# WeWyAn.net
KiCad netlist of a schematic drawn in EAGLE
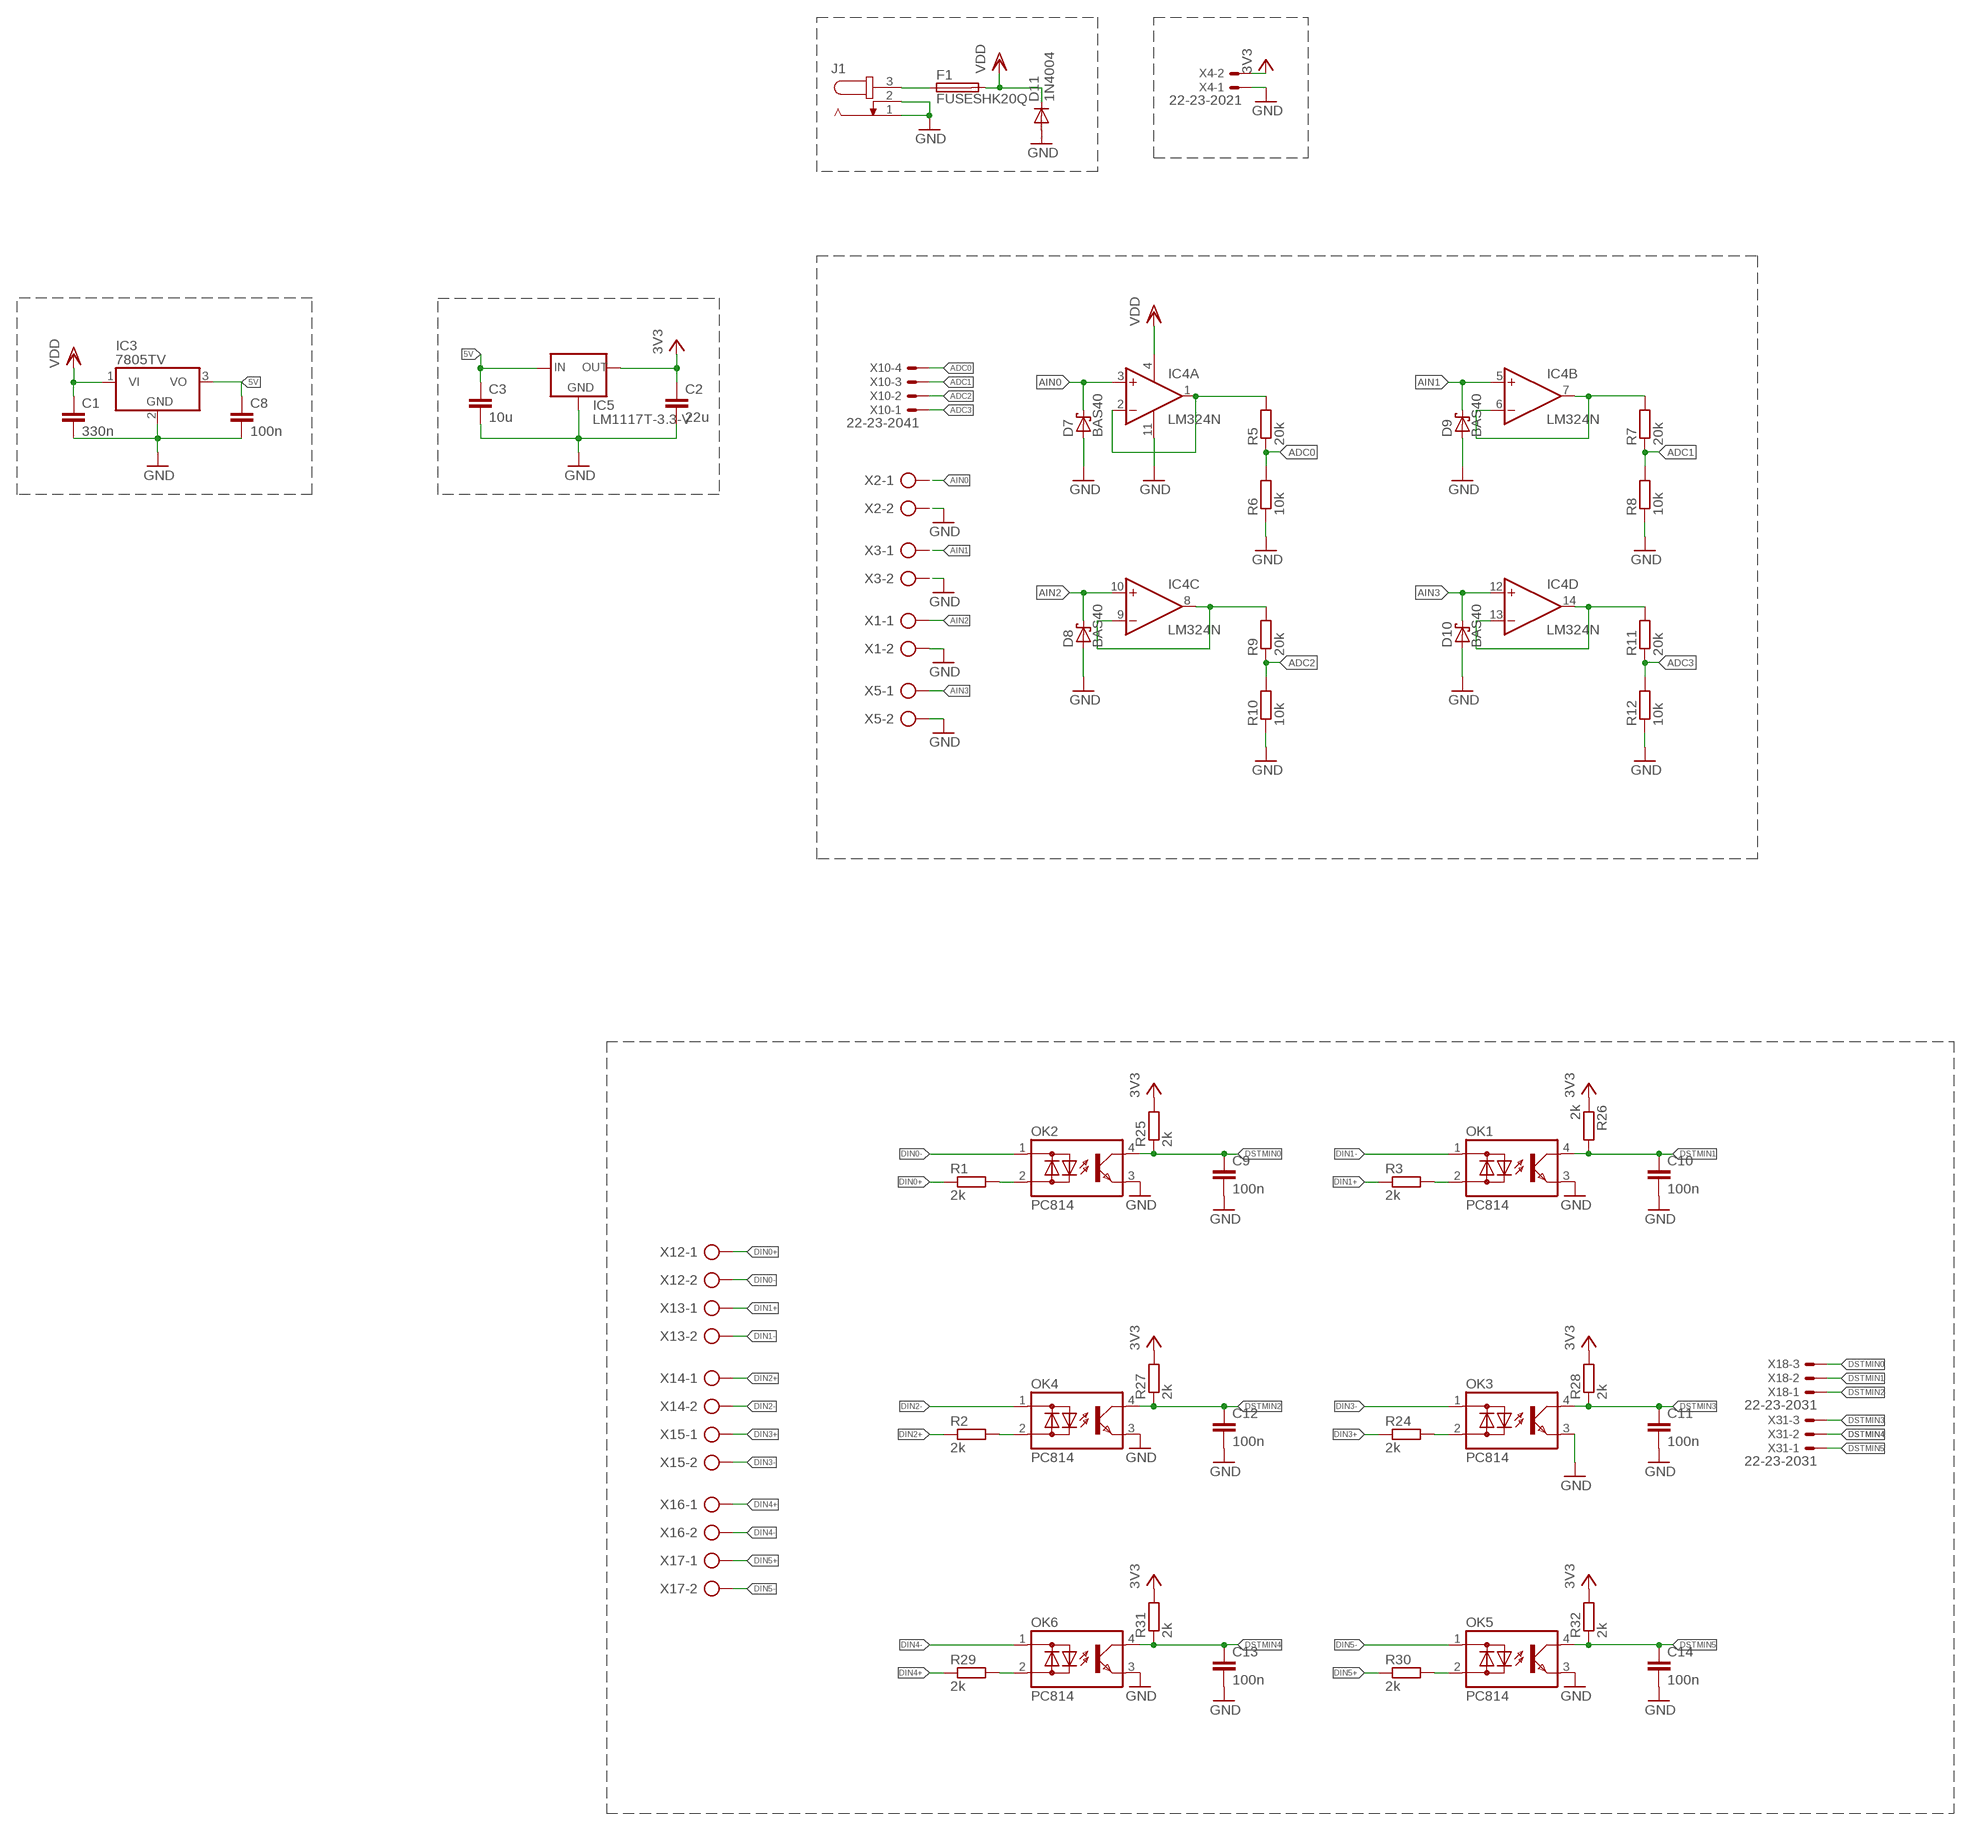
[diagram p0: schematic, sheet 1, part 1 of 2]
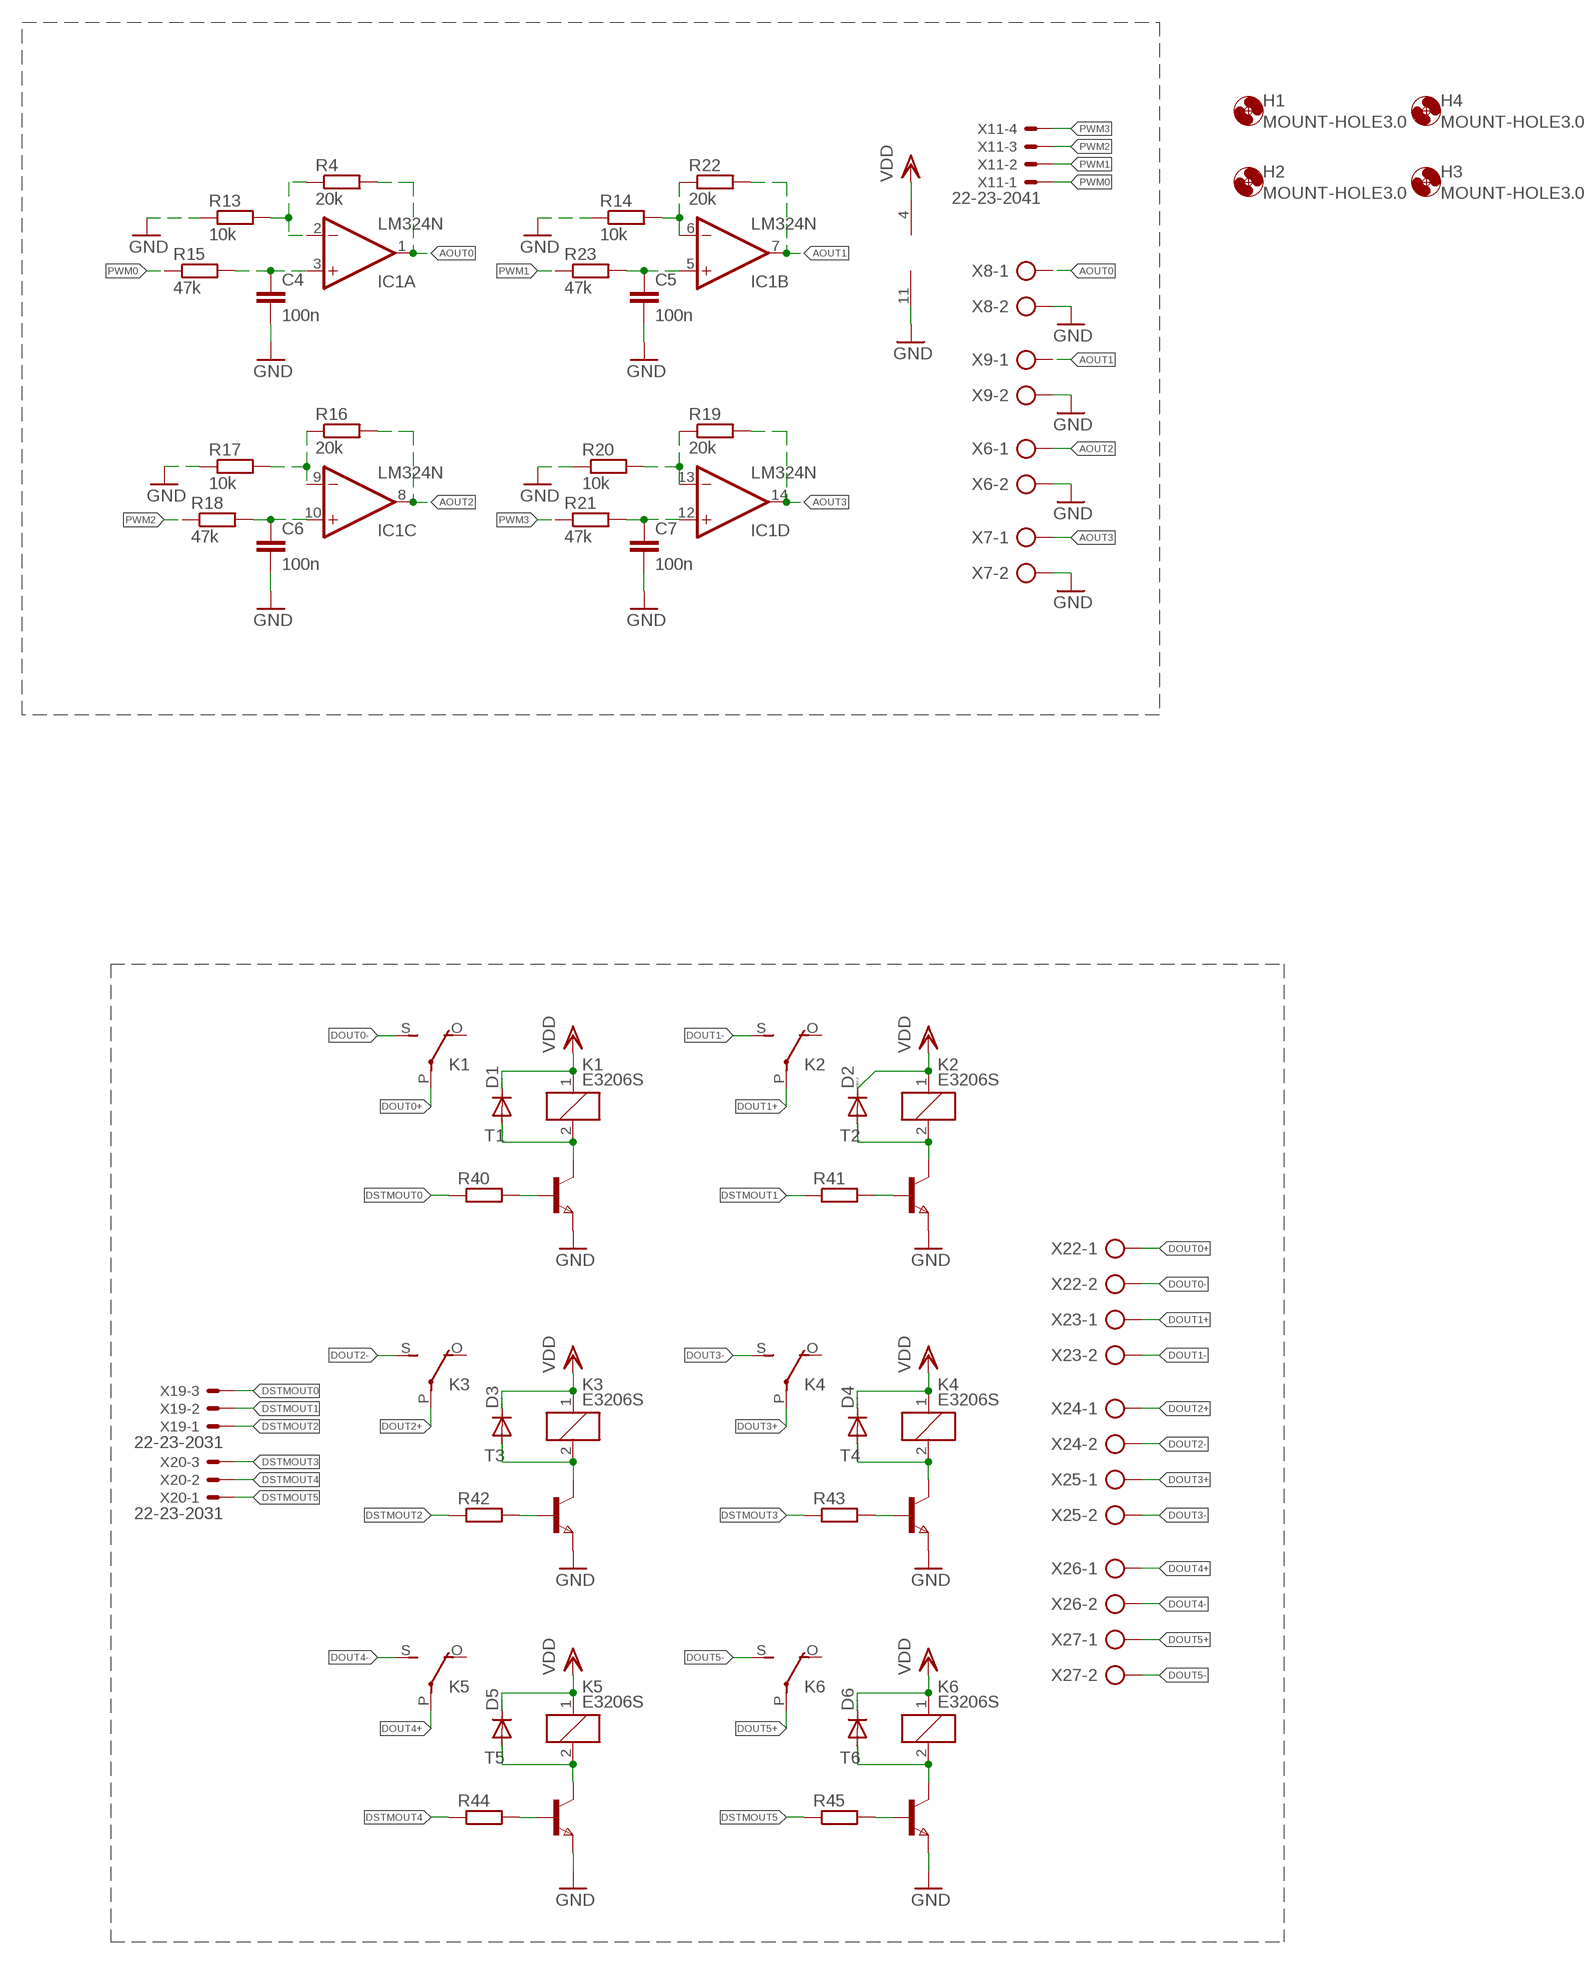
[diagram p1: schematic, sheet 1, part 2 of 2]

(export (version "E")
  (design (tool "Eeschema 10.0.6"))
  (components
    (comp (ref "C1")
      (value "330n")
      (footprint "eagle-import:C0603")
      (libsource (lib "eagle-import") (part "rcl_334_C-EUC0603"))
    )
    (comp (ref "C2")
      (value "22u")
      (footprint "eagle-import:C0603K")
      (libsource (lib "eagle-import") (part "C-EUC0603K"))
    )
    (comp (ref "C3")
      (value "10u")
      (footprint "eagle-import:C0603K")
      (libsource (lib "eagle-import") (part "C-EUC0603K"))
    )
    (comp (ref "C4")
      (value "100n")
      (footprint "eagle-import:C0603K")
      (libsource (lib "eagle-import") (part "C-EUC0603K"))
    )
    (comp (ref "C5")
      (value "100n")
      (footprint "eagle-import:C0603K")
      (libsource (lib "eagle-import") (part "C-EUC0603K"))
    )
    (comp (ref "C6")
      (value "100n")
      (footprint "eagle-import:C0603K")
      (libsource (lib "eagle-import") (part "C-EUC0603K"))
    )
    (comp (ref "C7")
      (value "100n")
      (footprint "eagle-import:C0603K")
      (libsource (lib "eagle-import") (part "C-EUC0603K"))
    )
    (comp (ref "C8")
      (value "100n")
      (footprint "eagle-import:C0603")
      (libsource (lib "eagle-import") (part "rcl_334_C-EUC0603"))
    )
    (comp (ref "C9")
      (value "100n")
      (footprint "eagle-import:C0603")
      (libsource (lib "eagle-import") (part "rcl_334_C-EUC0603"))
    )
    (comp (ref "C10")
      (value "100n")
      (footprint "eagle-import:C0603")
      (libsource (lib "eagle-import") (part "rcl_334_C-EUC0603"))
    )
    (comp (ref "C11")
      (value "100n")
      (footprint "eagle-import:C0603")
      (libsource (lib "eagle-import") (part "rcl_334_C-EUC0603"))
    )
    (comp (ref "C12")
      (value "100n")
      (footprint "eagle-import:C0603")
      (libsource (lib "eagle-import") (part "rcl_334_C-EUC0603"))
    )
    (comp (ref "C13")
      (value "100n")
      (footprint "eagle-import:C0603")
      (libsource (lib "eagle-import") (part "rcl_334_C-EUC0603"))
    )
    (comp (ref "C14")
      (value "100n")
      (footprint "eagle-import:C0603")
      (libsource (lib "eagle-import") (part "rcl_334_C-EUC0603"))
    )
    (comp (ref "D1")
      (value "DIODE-DO214AC")
      (footprint "eagle-import:DO214AC")
      (libsource (lib "eagle-import") (part "DIODE-DO214AC"))
    )
    (comp (ref "D2")
      (value "DIODE-DO214AC")
      (footprint "eagle-import:DO214AC")
      (libsource (lib "eagle-import") (part "DIODE-DO214AC"))
    )
    (comp (ref "D3")
      (value "DIODE-DO214AC")
      (footprint "eagle-import:DO214AC")
      (libsource (lib "eagle-import") (part "DIODE-DO214AC"))
    )
    (comp (ref "D4")
      (value "DIODE-DO214AC")
      (footprint "eagle-import:DO214AC")
      (libsource (lib "eagle-import") (part "DIODE-DO214AC"))
    )
    (comp (ref "D5")
      (value "DIODE-DO214AC")
      (footprint "eagle-import:DO214AC")
      (libsource (lib "eagle-import") (part "DIODE-DO214AC"))
    )
    (comp (ref "D6")
      (value "DIODE-DO214AC")
      (footprint "eagle-import:DO214AC")
      (libsource (lib "eagle-import") (part "DIODE-DO214AC"))
    )
    (comp (ref "D7")
      (value "BAS40")
      (footprint "eagle-import:SOT23")
      (libsource (lib "eagle-import") (part "BAS40"))
    )
    (comp (ref "D8")
      (value "BAS40")
      (footprint "eagle-import:SOT23")
      (libsource (lib "eagle-import") (part "BAS40"))
    )
    (comp (ref "D9")
      (value "BAS40")
      (footprint "eagle-import:SOT23")
      (libsource (lib "eagle-import") (part "BAS40"))
    )
    (comp (ref "D10")
      (value "BAS40")
      (footprint "eagle-import:SOT23")
      (libsource (lib "eagle-import") (part "BAS40"))
    )
    (comp (ref "D11")
      (value "1N4004")
      (footprint "eagle-import:DO41-10")
      (libsource (lib "eagle-import") (part "1N4004"))
    )
    (comp (ref "F1")
      (value "FUSESHK20Q")
      (footprint "eagle-import:SHK20Q")
      (libsource (lib "eagle-import") (part "FUSESHK20Q"))
    )
    (comp (ref "H1")
      (value "MOUNT-HOLE3.0")
      (footprint "eagle-import:3,0")
      (libsource (lib "eagle-import") (part "MOUNT-HOLE3.0"))
    )
    (comp (ref "H2")
      (value "MOUNT-HOLE3.0")
      (footprint "eagle-import:3,0")
      (libsource (lib "eagle-import") (part "MOUNT-HOLE3.0"))
    )
    (comp (ref "H3")
      (value "MOUNT-HOLE3.0")
      (footprint "eagle-import:3,0")
      (libsource (lib "eagle-import") (part "MOUNT-HOLE3.0"))
    )
    (comp (ref "H4")
      (value "MOUNT-HOLE3.0")
      (footprint "eagle-import:3,0")
      (libsource (lib "eagle-import") (part "MOUNT-HOLE3.0"))
    )
    (comp (ref "IC1")
      (value "LM324N")
      (footprint "eagle-import:DIL14")
      (libsource (lib "eagle-import") (part "LM324N"))
    )
    (comp (ref "IC3")
      (value "7805TV")
      (footprint "eagle-import:TO220V")
      (libsource (lib "eagle-import") (part "78TV05"))
    )
    (comp (ref "IC4")
      (value "LM324N")
      (footprint "eagle-import:DIL14")
      (libsource (lib "eagle-import") (part "LM324N"))
    )
    (comp (ref "IC5")
      (value "LM1117T-3.3-V")
      (footprint "eagle-import:TO220V")
      (libsource (lib "eagle-import") (part "LM1117T--V3.3"))
    )
    (comp (ref "J1")
      (value "JACK-PLUG1")
      (footprint "eagle-import:SPC4078")
      (libsource (lib "eagle-import") (part "JACK-PLUG1"))
    )
    (comp (ref "K1")
      (value "E3206S")
      (footprint "eagle-import:E3206S")
      (libsource (lib "eagle-import") (part "E3206S"))
    )
    (comp (ref "K2")
      (value "E3206S")
      (footprint "eagle-import:E3206S")
      (libsource (lib "eagle-import") (part "E3206S"))
    )
    (comp (ref "K3")
      (value "E3206S")
      (footprint "eagle-import:E3206S")
      (libsource (lib "eagle-import") (part "E3206S"))
    )
    (comp (ref "K4")
      (value "E3206S")
      (footprint "eagle-import:E3206S")
      (libsource (lib "eagle-import") (part "E3206S"))
    )
    (comp (ref "K5")
      (value "E3206S")
      (footprint "eagle-import:E3206S")
      (libsource (lib "eagle-import") (part "E3206S"))
    )
    (comp (ref "K6")
      (value "E3206S")
      (footprint "eagle-import:E3206S")
      (libsource (lib "eagle-import") (part "E3206S"))
    )
    (comp (ref "OK1")
      (value "PC814")
      (footprint "eagle-import:DIL04")
      (libsource (lib "eagle-import") (part "PC814"))
    )
    (comp (ref "OK2")
      (value "PC814")
      (footprint "eagle-import:DIL04")
      (libsource (lib "eagle-import") (part "PC814"))
    )
    (comp (ref "OK3")
      (value "PC814")
      (footprint "eagle-import:DIL04")
      (libsource (lib "eagle-import") (part "PC814"))
    )
    (comp (ref "OK4")
      (value "PC814")
      (footprint "eagle-import:DIL04")
      (libsource (lib "eagle-import") (part "PC814"))
    )
    (comp (ref "OK5")
      (value "PC814")
      (footprint "eagle-import:DIL04")
      (libsource (lib "eagle-import") (part "PC814"))
    )
    (comp (ref "OK6")
      (value "PC814")
      (footprint "eagle-import:DIL04")
      (libsource (lib "eagle-import") (part "PC814"))
    )
    (comp (ref "R1")
      (value "2k")
      (footprint "eagle-import:R0603")
      (libsource (lib "eagle-import") (part "R-EU_R0603"))
    )
    (comp (ref "R2")
      (value "2k")
      (footprint "eagle-import:R0603")
      (libsource (lib "eagle-import") (part "R-EU_R0603"))
    )
    (comp (ref "R3")
      (value "2k")
      (footprint "eagle-import:R0603")
      (libsource (lib "eagle-import") (part "R-EU_R0603"))
    )
    (comp (ref "R4")
      (value "20k")
      (footprint "eagle-import:R0603")
      (libsource (lib "eagle-import") (part "R-EU_R0603"))
    )
    (comp (ref "R5")
      (value "20k")
      (footprint "eagle-import:R0603")
      (libsource (lib "eagle-import") (part "R-EU_R0603"))
    )
    (comp (ref "R6")
      (value "10k")
      (footprint "eagle-import:R0603")
      (libsource (lib "eagle-import") (part "R-EU_R0603"))
    )
    (comp (ref "R7")
      (value "20k")
      (footprint "eagle-import:R0603")
      (libsource (lib "eagle-import") (part "R-EU_R0603"))
    )
    (comp (ref "R8")
      (value "10k")
      (footprint "eagle-import:R0603")
      (libsource (lib "eagle-import") (part "R-EU_R0603"))
    )
    (comp (ref "R9")
      (value "20k")
      (footprint "eagle-import:R0603")
      (libsource (lib "eagle-import") (part "R-EU_R0603"))
    )
    (comp (ref "R10")
      (value "10k")
      (footprint "eagle-import:R0603")
      (libsource (lib "eagle-import") (part "R-EU_R0603"))
    )
    (comp (ref "R11")
      (value "20k")
      (footprint "eagle-import:R0603")
      (libsource (lib "eagle-import") (part "R-EU_R0603"))
    )
    (comp (ref "R12")
      (value "10k")
      (footprint "eagle-import:R0603")
      (libsource (lib "eagle-import") (part "R-EU_R0603"))
    )
    (comp (ref "R13")
      (value "10k")
      (footprint "eagle-import:R0603")
      (libsource (lib "eagle-import") (part "R-EU_R0603"))
    )
    (comp (ref "R14")
      (value "10k")
      (footprint "eagle-import:R0603")
      (libsource (lib "eagle-import") (part "R-EU_R0603"))
    )
    (comp (ref "R15")
      (value "47k")
      (footprint "eagle-import:R0603")
      (libsource (lib "eagle-import") (part "R-EU_R0603"))
    )
    (comp (ref "R16")
      (value "20k")
      (footprint "eagle-import:R0603")
      (libsource (lib "eagle-import") (part "R-EU_R0603"))
    )
    (comp (ref "R17")
      (value "10k")
      (footprint "eagle-import:R0603")
      (libsource (lib "eagle-import") (part "R-EU_R0603"))
    )
    (comp (ref "R18")
      (value "47k")
      (footprint "eagle-import:R0603")
      (libsource (lib "eagle-import") (part "R-EU_R0603"))
    )
    (comp (ref "R19")
      (value "20k")
      (footprint "eagle-import:R0603")
      (libsource (lib "eagle-import") (part "R-EU_R0603"))
    )
    (comp (ref "R20")
      (value "10k")
      (footprint "eagle-import:R0603")
      (libsource (lib "eagle-import") (part "R-EU_R0603"))
    )
    (comp (ref "R21")
      (value "47k")
      (footprint "eagle-import:R0603")
      (libsource (lib "eagle-import") (part "R-EU_R0603"))
    )
    (comp (ref "R22")
      (value "20k")
      (footprint "eagle-import:R0603")
      (libsource (lib "eagle-import") (part "R-EU_R0603"))
    )
    (comp (ref "R23")
      (value "47k")
      (footprint "eagle-import:R0603")
      (libsource (lib "eagle-import") (part "R-EU_R0603"))
    )
    (comp (ref "R24")
      (value "2k")
      (footprint "eagle-import:R0603")
      (libsource (lib "eagle-import") (part "R-EU_R0603"))
    )
    (comp (ref "R25")
      (value "2k")
      (footprint "eagle-import:R0603")
      (libsource (lib "eagle-import") (part "R-EU_R0603"))
    )
    (comp (ref "R26")
      (value "2k")
      (footprint "eagle-import:R0603")
      (libsource (lib "eagle-import") (part "R-EU_R0603"))
    )
    (comp (ref "R27")
      (value "2k")
      (footprint "eagle-import:R0603")
      (libsource (lib "eagle-import") (part "R-EU_R0603"))
    )
    (comp (ref "R28")
      (value "2k")
      (footprint "eagle-import:R0603")
      (libsource (lib "eagle-import") (part "R-EU_R0603"))
    )
    (comp (ref "R29")
      (value "2k")
      (footprint "eagle-import:R0603")
      (libsource (lib "eagle-import") (part "R-EU_R0603"))
    )
    (comp (ref "R30")
      (value "2k")
      (footprint "eagle-import:R0603")
      (libsource (lib "eagle-import") (part "R-EU_R0603"))
    )
    (comp (ref "R31")
      (value "2k")
      (footprint "eagle-import:R0603")
      (libsource (lib "eagle-import") (part "R-EU_R0603"))
    )
    (comp (ref "R32")
      (value "2k")
      (footprint "eagle-import:R0603")
      (libsource (lib "eagle-import") (part "R-EU_R0603"))
    )
    (comp (ref "R40")
      (value "R-EU_R0603")
      (footprint "eagle-import:R0603")
      (libsource (lib "eagle-import") (part "rcl_334_R-EU_R0603"))
    )
    (comp (ref "R41")
      (value "R-EU_R0603")
      (footprint "eagle-import:R0603")
      (libsource (lib "eagle-import") (part "rcl_334_R-EU_R0603"))
    )
    (comp (ref "R42")
      (value "R-EU_R0603")
      (footprint "eagle-import:R0603")
      (libsource (lib "eagle-import") (part "rcl_334_R-EU_R0603"))
    )
    (comp (ref "R43")
      (value "R-EU_R0603")
      (footprint "eagle-import:R0603")
      (libsource (lib "eagle-import") (part "rcl_334_R-EU_R0603"))
    )
    (comp (ref "R44")
      (value "R-EU_R0603")
      (footprint "eagle-import:R0603")
      (libsource (lib "eagle-import") (part "rcl_334_R-EU_R0603"))
    )
    (comp (ref "R45")
      (value "R-EU_R0603")
      (footprint "eagle-import:R0603")
      (libsource (lib "eagle-import") (part "rcl_334_R-EU_R0603"))
    )
    (comp (ref "T1")
      (value "NPNSOT223")
      (footprint "eagle-import:SOT223")
      (fields (field (name "MPN") "DJT4031N-13"))
      (libsource (lib "eagle-import") (part "NPNSOT223"))
    )
    (comp (ref "T2")
      (value "NPNSOT223")
      (footprint "eagle-import:SOT223")
      (fields (field (name "MPN") "DJT4031N-13"))
      (libsource (lib "eagle-import") (part "NPNSOT223"))
    )
    (comp (ref "T3")
      (value "NPNSOT223")
      (footprint "eagle-import:SOT223")
      (fields (field (name "MPN") "DJT4031N-13"))
      (libsource (lib "eagle-import") (part "NPNSOT223"))
    )
    (comp (ref "T4")
      (value "NPNSOT223")
      (footprint "eagle-import:SOT223")
      (fields (field (name "MPN") "DJT4031N-13"))
      (libsource (lib "eagle-import") (part "NPNSOT223"))
    )
    (comp (ref "T5")
      (value "NPNSOT223")
      (footprint "eagle-import:SOT223")
      (fields (field (name "MPN") "DJT4031N-13"))
      (libsource (lib "eagle-import") (part "NPNSOT223"))
    )
    (comp (ref "T6")
      (value "NPNSOT223")
      (footprint "eagle-import:SOT223")
      (fields (field (name "MPN") "DJT4031N-13"))
      (libsource (lib "eagle-import") (part "NPNSOT223"))
    )
    (comp (ref "X1")
      (value "AK500/2-H")
      (footprint "eagle-import:AK500_2-H")
      (libsource (lib "eagle-import") (part "AK500/2-H"))
    )
    (comp (ref "X2")
      (value "AK500/2-H")
      (footprint "eagle-import:AK500_2-H")
      (libsource (lib "eagle-import") (part "AK500/2-H"))
    )
    (comp (ref "X3")
      (value "AK500/2-H")
      (footprint "eagle-import:AK500_2-H")
      (libsource (lib "eagle-import") (part "AK500/2-H"))
    )
    (comp (ref "X4")
      (value "22-23-2021")
      (footprint "eagle-import:22-23-2021")
      (fields (field (name "MF") "MOLEX"))
      (libsource (lib "eagle-import") (part "22-23-2021"))
    )
    (comp (ref "X5")
      (value "AK500/2-H")
      (footprint "eagle-import:AK500_2-H")
      (libsource (lib "eagle-import") (part "AK500/2-H"))
    )
    (comp (ref "X6")
      (value "AK500/2-H")
      (footprint "eagle-import:AK500_2-H")
      (libsource (lib "eagle-import") (part "AK500/2-H"))
    )
    (comp (ref "X7")
      (value "AK500/2-H")
      (footprint "eagle-import:AK500_2-H")
      (libsource (lib "eagle-import") (part "AK500/2-H"))
    )
    (comp (ref "X8")
      (value "AK500/2-H")
      (footprint "eagle-import:AK500_2-H")
      (libsource (lib "eagle-import") (part "AK500/2-H"))
    )
    (comp (ref "X9")
      (value "AK500/2-H")
      (footprint "eagle-import:AK500_2-H")
      (libsource (lib "eagle-import") (part "AK500/2-H"))
    )
    (comp (ref "X10")
      (value "22-23-2041")
      (footprint "eagle-import:22-23-2041")
      (fields (field (name "MF") "MOLEX"))
      (libsource (lib "eagle-import") (part "22-23-2041"))
    )
    (comp (ref "X11")
      (value "22-23-2041")
      (footprint "eagle-import:22-23-2041")
      (fields (field (name "MF") "MOLEX"))
      (libsource (lib "eagle-import") (part "22-23-2041"))
    )
    (comp (ref "X12")
      (value "AK500/2-H")
      (footprint "eagle-import:AK500_2-H")
      (libsource (lib "eagle-import") (part "AK500/2-H"))
    )
    (comp (ref "X13")
      (value "AK500/2-H")
      (footprint "eagle-import:AK500_2-H")
      (libsource (lib "eagle-import") (part "AK500/2-H"))
    )
    (comp (ref "X14")
      (value "AK500/2-H")
      (footprint "eagle-import:AK500_2-H")
      (libsource (lib "eagle-import") (part "AK500/2-H"))
    )
    (comp (ref "X15")
      (value "AK500/2-H")
      (footprint "eagle-import:AK500_2-H")
      (libsource (lib "eagle-import") (part "AK500/2-H"))
    )
    (comp (ref "X16")
      (value "AK500/2-H")
      (footprint "eagle-import:AK500_2-H")
      (libsource (lib "eagle-import") (part "AK500/2-H"))
    )
    (comp (ref "X17")
      (value "AK500/2-H")
      (footprint "eagle-import:AK500_2-H")
      (libsource (lib "eagle-import") (part "AK500/2-H"))
    )
    (comp (ref "X18")
      (value "22-23-2031")
      (footprint "eagle-import:22-23-2031")
      (fields (field (name "MF") "MOLEX"))
      (libsource (lib "eagle-import") (part "22-23-2031"))
    )
    (comp (ref "X19")
      (value "22-23-2031")
      (footprint "eagle-import:22-23-2031")
      (fields (field (name "MF") "MOLEX"))
      (libsource (lib "eagle-import") (part "22-23-2031"))
    )
    (comp (ref "X20")
      (value "22-23-2031")
      (footprint "eagle-import:22-23-2031")
      (fields (field (name "MF") "MOLEX"))
      (libsource (lib "eagle-import") (part "22-23-2031"))
    )
    (comp (ref "X22")
      (value "AK500/2-H")
      (footprint "eagle-import:AK500_2-H")
      (libsource (lib "eagle-import") (part "AK500/2-H"))
    )
    (comp (ref "X23")
      (value "AK500/2-H")
      (footprint "eagle-import:AK500_2-H")
      (libsource (lib "eagle-import") (part "AK500/2-H"))
    )
    (comp (ref "X24")
      (value "AK500/2-H")
      (footprint "eagle-import:AK500_2-H")
      (libsource (lib "eagle-import") (part "AK500/2-H"))
    )
    (comp (ref "X25")
      (value "AK500/2-H")
      (footprint "eagle-import:AK500_2-H")
      (libsource (lib "eagle-import") (part "AK500/2-H"))
    )
    (comp (ref "X26")
      (value "AK500/2-H")
      (footprint "eagle-import:AK500_2-H")
      (libsource (lib "eagle-import") (part "AK500/2-H"))
    )
    (comp (ref "X27")
      (value "AK500/2-H")
      (footprint "eagle-import:AK500_2-H")
      (libsource (lib "eagle-import") (part "AK500/2-H"))
    )
    (comp (ref "X31")
      (value "22-23-2031")
      (footprint "eagle-import:22-23-2031")
      (fields (field (name "MF") "MOLEX"))
      (libsource (lib "eagle-import") (part "22-23-2031"))
    )
  )
  (nets
    (net (code "1") (name "3V3") (class "Default")
      (node (ref "C2") (pin "1") (pinfunction "1_1") (pintype "passive"))
      (node (ref "IC5") (pin "2") (pinfunction "OUT_2") (pintype "passive"))
      (node (ref "R25") (pin "2") (pinfunction "2_2") (pintype "passive"))
      (node (ref "R26") (pin "1") (pinfunction "1_1") (pintype "passive"))
      (node (ref "R27") (pin "2") (pinfunction "2_2") (pintype "passive"))
      (node (ref "R28") (pin "2") (pinfunction "2_2") (pintype "passive"))
      (node (ref "R31") (pin "2") (pinfunction "2_2") (pintype "passive"))
      (node (ref "R32") (pin "2") (pinfunction "2_2") (pintype "passive"))
      (node (ref "X4") (pin "2") (pinfunction "S_2") (pintype "passive"))
    )
    (net (code "2") (name "5V") (class "Default")
      (node (ref "C3") (pin "1") (pinfunction "1_1") (pintype "passive"))
      (node (ref "C8") (pin "1") (pinfunction "1_1") (pintype "passive"))
      (node (ref "IC3") (pin "3") (pinfunction "VO_3") (pintype "passive"))
      (node (ref "IC5") (pin "3") (pinfunction "IN_3") (pintype "input"))
    )
    (net (code "3") (name "ADC0") (class "Default")
      (node (ref "R5") (pin "1") (pinfunction "1_1") (pintype "passive"))
      (node (ref "R6") (pin "2") (pinfunction "2_2") (pintype "passive"))
      (node (ref "X10") (pin "4") (pinfunction "S_4") (pintype "passive"))
    )
    (net (code "4") (name "ADC1") (class "Default")
      (node (ref "R7") (pin "1") (pinfunction "1_1") (pintype "passive"))
      (node (ref "R8") (pin "2") (pinfunction "2_2") (pintype "passive"))
      (node (ref "X10") (pin "3") (pinfunction "S_3") (pintype "passive"))
    )
    (net (code "5") (name "ADC2") (class "Default")
      (node (ref "R10") (pin "2") (pinfunction "2_2") (pintype "passive"))
      (node (ref "R9") (pin "1") (pinfunction "1_1") (pintype "passive"))
      (node (ref "X10") (pin "2") (pinfunction "S_2") (pintype "passive"))
    )
    (net (code "6") (name "ADC3") (class "Default")
      (node (ref "R11") (pin "1") (pinfunction "1_1") (pintype "passive"))
      (node (ref "R12") (pin "2") (pinfunction "2_2") (pintype "passive"))
      (node (ref "X10") (pin "1") (pinfunction "S_1") (pintype "passive"))
    )
    (net (code "7") (name "AIN0") (class "Default")
      (node (ref "D7") (pin "3") (pinfunction "C_3") (pintype "passive"))
      (node (ref "IC4") (pin "3") (pinfunction "+IN_3") (pintype "input"))
      (node (ref "X2") (pin "1") (pinfunction "KL_1") (pintype "passive"))
    )
    (net (code "8") (name "AIN1") (class "Default")
      (node (ref "D9") (pin "3") (pinfunction "C_3") (pintype "passive"))
      (node (ref "IC4") (pin "5") (pinfunction "+IN_5") (pintype "input"))
      (node (ref "X3") (pin "1") (pinfunction "KL_1") (pintype "passive"))
    )
    (net (code "9") (name "AIN2") (class "Default")
      (node (ref "D8") (pin "3") (pinfunction "C_3") (pintype "passive"))
      (node (ref "IC4") (pin "10") (pinfunction "+IN_10") (pintype "input"))
      (node (ref "X1") (pin "1") (pinfunction "KL_1") (pintype "passive"))
    )
    (net (code "10") (name "AIN3") (class "Default")
      (node (ref "D10") (pin "3") (pinfunction "C_3") (pintype "passive"))
      (node (ref "IC4") (pin "12") (pinfunction "+IN_12") (pintype "input"))
      (node (ref "X5") (pin "1") (pinfunction "KL_1") (pintype "passive"))
    )
    (net (code "11") (name "AOUT0") (class "Default")
      (node (ref "IC1") (pin "1") (pinfunction "OUT_1") (pintype "output"))
      (node (ref "R4") (pin "2") (pinfunction "2_2") (pintype "passive"))
      (node (ref "X8") (pin "1") (pinfunction "KL_1") (pintype "passive"))
    )
    (net (code "12") (name "AOUT1") (class "Default")
      (node (ref "IC1") (pin "7") (pinfunction "OUT_7") (pintype "output"))
      (node (ref "R22") (pin "2") (pinfunction "2_2") (pintype "passive"))
      (node (ref "X9") (pin "1") (pinfunction "KL_1") (pintype "passive"))
    )
    (net (code "13") (name "AOUT2") (class "Default")
      (node (ref "IC1") (pin "8") (pinfunction "OUT_8") (pintype "output"))
      (node (ref "R16") (pin "2") (pinfunction "2_2") (pintype "passive"))
      (node (ref "X6") (pin "1") (pinfunction "KL_1") (pintype "passive"))
    )
    (net (code "14") (name "AOUT3") (class "Default")
      (node (ref "IC1") (pin "14") (pinfunction "OUT_14") (pintype "output"))
      (node (ref "R19") (pin "2") (pinfunction "2_2") (pintype "passive"))
      (node (ref "X7") (pin "1") (pinfunction "KL_1") (pintype "passive"))
    )
    (net (code "15") (name "DIN0+") (class "Default")
      (node (ref "R1") (pin "1") (pinfunction "1_1") (pintype "passive"))
      (node (ref "X12") (pin "1") (pinfunction "KL_1") (pintype "passive"))
    )
    (net (code "16") (name "DIN0-") (class "Default")
      (node (ref "OK2") (pin "1") (pinfunction "AC1_1") (pintype "passive"))
      (node (ref "X12") (pin "2") (pinfunction "KL_2") (pintype "passive"))
    )
    (net (code "17") (name "DIN1+") (class "Default")
      (node (ref "R3") (pin "1") (pinfunction "1_1") (pintype "passive"))
      (node (ref "X13") (pin "1") (pinfunction "KL_1") (pintype "passive"))
    )
    (net (code "18") (name "DIN1-") (class "Default")
      (node (ref "OK1") (pin "1") (pinfunction "AC1_1") (pintype "passive"))
      (node (ref "X13") (pin "2") (pinfunction "KL_2") (pintype "passive"))
    )
    (net (code "19") (name "DIN2+") (class "Default")
      (node (ref "R2") (pin "1") (pinfunction "1_1") (pintype "passive"))
      (node (ref "X14") (pin "1") (pinfunction "KL_1") (pintype "passive"))
    )
    (net (code "20") (name "DIN2-") (class "Default")
      (node (ref "OK4") (pin "1") (pinfunction "AC1_1") (pintype "passive"))
      (node (ref "X14") (pin "2") (pinfunction "KL_2") (pintype "passive"))
    )
    (net (code "21") (name "DIN3+") (class "Default")
      (node (ref "R24") (pin "1") (pinfunction "1_1") (pintype "passive"))
      (node (ref "X15") (pin "1") (pinfunction "KL_1") (pintype "passive"))
    )
    (net (code "22") (name "DIN3-") (class "Default")
      (node (ref "OK3") (pin "1") (pinfunction "AC1_1") (pintype "passive"))
      (node (ref "X15") (pin "2") (pinfunction "KL_2") (pintype "passive"))
    )
    (net (code "23") (name "DIN4+") (class "Default")
      (node (ref "R29") (pin "1") (pinfunction "1_1") (pintype "passive"))
      (node (ref "X16") (pin "1") (pinfunction "KL_1") (pintype "passive"))
    )
    (net (code "24") (name "DIN4-") (class "Default")
      (node (ref "OK6") (pin "1") (pinfunction "AC1_1") (pintype "passive"))
      (node (ref "X16") (pin "2") (pinfunction "KL_2") (pintype "passive"))
    )
    (net (code "25") (name "DIN5+") (class "Default")
      (node (ref "R30") (pin "1") (pinfunction "1_1") (pintype "passive"))
      (node (ref "X17") (pin "1") (pinfunction "KL_1") (pintype "passive"))
    )
    (net (code "26") (name "DIN5-") (class "Default")
      (node (ref "OK5") (pin "1") (pinfunction "AC1_1") (pintype "passive"))
      (node (ref "X17") (pin "2") (pinfunction "KL_2") (pintype "passive"))
    )
    (net (code "27") (name "DOUT0+") (class "Default")
      (node (ref "K1") (pin "P") (pinfunction "P_P") (pintype "passive"))
      (node (ref "X22") (pin "1") (pinfunction "KL_1") (pintype "passive"))
    )
    (net (code "28") (name "DOUT0-") (class "Default")
      (node (ref "K1") (pin "S") (pinfunction "S_S") (pintype "passive"))
      (node (ref "X22") (pin "2") (pinfunction "KL_2") (pintype "passive"))
    )
    (net (code "29") (name "DOUT1+") (class "Default")
      (node (ref "K2") (pin "P") (pinfunction "P_P") (pintype "passive"))
      (node (ref "X23") (pin "1") (pinfunction "KL_1") (pintype "passive"))
    )
    (net (code "30") (name "DOUT1-") (class "Default")
      (node (ref "K2") (pin "S") (pinfunction "S_S") (pintype "passive"))
      (node (ref "X23") (pin "2") (pinfunction "KL_2") (pintype "passive"))
    )
    (net (code "31") (name "DOUT2+") (class "Default")
      (node (ref "K3") (pin "P") (pinfunction "P_P") (pintype "passive"))
      (node (ref "X24") (pin "1") (pinfunction "KL_1") (pintype "passive"))
    )
    (net (code "32") (name "DOUT2-") (class "Default")
      (node (ref "K3") (pin "S") (pinfunction "S_S") (pintype "passive"))
      (node (ref "X24") (pin "2") (pinfunction "KL_2") (pintype "passive"))
    )
    (net (code "33") (name "DOUT3+") (class "Default")
      (node (ref "K4") (pin "P") (pinfunction "P_P") (pintype "passive"))
      (node (ref "X25") (pin "1") (pinfunction "KL_1") (pintype "passive"))
    )
    (net (code "34") (name "DOUT3-") (class "Default")
      (node (ref "K4") (pin "S") (pinfunction "S_S") (pintype "passive"))
      (node (ref "X25") (pin "2") (pinfunction "KL_2") (pintype "passive"))
    )
    (net (code "35") (name "DOUT4+") (class "Default")
      (node (ref "K5") (pin "P") (pinfunction "P_P") (pintype "passive"))
      (node (ref "X26") (pin "1") (pinfunction "KL_1") (pintype "passive"))
    )
    (net (code "36") (name "DOUT4-") (class "Default")
      (node (ref "K5") (pin "S") (pinfunction "S_S") (pintype "passive"))
      (node (ref "X26") (pin "2") (pinfunction "KL_2") (pintype "passive"))
    )
    (net (code "37") (name "DOUT5+") (class "Default")
      (node (ref "K6") (pin "P") (pinfunction "P_P") (pintype "passive"))
      (node (ref "X27") (pin "1") (pinfunction "KL_1") (pintype "passive"))
    )
    (net (code "38") (name "DOUT5-") (class "Default")
      (node (ref "K6") (pin "S") (pinfunction "S_S") (pintype "passive"))
      (node (ref "X27") (pin "2") (pinfunction "KL_2") (pintype "passive"))
    )
    (net (code "39") (name "DSTMIN0") (class "Default")
      (node (ref "C9") (pin "1") (pinfunction "1_1") (pintype "passive"))
      (node (ref "OK2") (pin "4") (pinfunction "C_4") (pintype "passive"))
      (node (ref "R25") (pin "1") (pinfunction "1_1") (pintype "passive"))
      (node (ref "X18") (pin "3") (pinfunction "S_3") (pintype "passive"))
    )
    (net (code "40") (name "DSTMIN1") (class "Default")
      (node (ref "C10") (pin "1") (pinfunction "1_1") (pintype "passive"))
      (node (ref "OK1") (pin "4") (pinfunction "C_4") (pintype "passive"))
      (node (ref "R26") (pin "2") (pinfunction "2_2") (pintype "passive"))
      (node (ref "X18") (pin "2") (pinfunction "S_2") (pintype "passive"))
    )
    (net (code "41") (name "DSTMIN2") (class "Default")
      (node (ref "C12") (pin "1") (pinfunction "1_1") (pintype "passive"))
      (node (ref "OK4") (pin "4") (pinfunction "C_4") (pintype "passive"))
      (node (ref "R27") (pin "1") (pinfunction "1_1") (pintype "passive"))
      (node (ref "X18") (pin "1") (pinfunction "S_1") (pintype "passive"))
    )
    (net (code "42") (name "DSTMIN3") (class "Default")
      (node (ref "C11") (pin "1") (pinfunction "1_1") (pintype "passive"))
      (node (ref "OK3") (pin "4") (pinfunction "C_4") (pintype "passive"))
      (node (ref "R28") (pin "1") (pinfunction "1_1") (pintype "passive"))
      (node (ref "X31") (pin "3") (pinfunction "S_3") (pintype "passive"))
    )
    (net (code "43") (name "DSTMIN4") (class "Default")
      (node (ref "C13") (pin "1") (pinfunction "1_1") (pintype "passive"))
      (node (ref "OK6") (pin "4") (pinfunction "C_4") (pintype "passive"))
      (node (ref "R31") (pin "1") (pinfunction "1_1") (pintype "passive"))
      (node (ref "X31") (pin "2") (pinfunction "S_2") (pintype "passive"))
    )
    (net (code "44") (name "DSTMIN5") (class "Default")
      (node (ref "C14") (pin "1") (pinfunction "1_1") (pintype "passive"))
      (node (ref "OK5") (pin "4") (pinfunction "C_4") (pintype "passive"))
      (node (ref "R32") (pin "1") (pinfunction "1_1") (pintype "passive"))
      (node (ref "X31") (pin "1") (pinfunction "S_1") (pintype "passive"))
    )
    (net (code "45") (name "DSTMOUT0") (class "Default")
      (node (ref "R40") (pin "1") (pinfunction "1_1") (pintype "passive"))
      (node (ref "X19") (pin "3") (pinfunction "S_3") (pintype "passive"))
    )
    (net (code "46") (name "DSTMOUT1") (class "Default")
      (node (ref "R41") (pin "1") (pinfunction "1_1") (pintype "passive"))
      (node (ref "X19") (pin "2") (pinfunction "S_2") (pintype "passive"))
    )
    (net (code "47") (name "DSTMOUT2") (class "Default")
      (node (ref "R42") (pin "1") (pinfunction "1_1") (pintype "passive"))
      (node (ref "X19") (pin "1") (pinfunction "S_1") (pintype "passive"))
    )
    (net (code "48") (name "DSTMOUT3") (class "Default")
      (node (ref "R43") (pin "1") (pinfunction "1_1") (pintype "passive"))
      (node (ref "X20") (pin "3") (pinfunction "S_3") (pintype "passive"))
    )
    (net (code "49") (name "DSTMOUT4") (class "Default")
      (node (ref "R44") (pin "1") (pinfunction "1_1") (pintype "passive"))
      (node (ref "X20") (pin "2") (pinfunction "S_2") (pintype "passive"))
    )
    (net (code "50") (name "DSTMOUT5") (class "Default")
      (node (ref "R45") (pin "1") (pinfunction "1_1") (pintype "passive"))
      (node (ref "X20") (pin "1") (pinfunction "S_1") (pintype "passive"))
    )
    (net (code "51") (name "GND") (class "Default")
      (node (ref "C1") (pin "2") (pinfunction "2_2") (pintype "passive"))
      (node (ref "C10") (pin "2") (pinfunction "2_2") (pintype "passive"))
      (node (ref "C11") (pin "2") (pinfunction "2_2") (pintype "passive"))
      (node (ref "C12") (pin "2") (pinfunction "2_2") (pintype "passive"))
      (node (ref "C13") (pin "2") (pinfunction "2_2") (pintype "passive"))
      (node (ref "C14") (pin "2") (pinfunction "2_2") (pintype "passive"))
      (node (ref "C2") (pin "2") (pinfunction "2_2") (pintype "passive"))
      (node (ref "C3") (pin "2") (pinfunction "2_2") (pintype "passive"))
      (node (ref "C4") (pin "2") (pinfunction "2_2") (pintype "passive"))
      (node (ref "C5") (pin "2") (pinfunction "2_2") (pintype "passive"))
      (node (ref "C6") (pin "2") (pinfunction "2_2") (pintype "passive"))
      (node (ref "C7") (pin "2") (pinfunction "2_2") (pintype "passive"))
      (node (ref "C8") (pin "2") (pinfunction "2_2") (pintype "passive"))
      (node (ref "C9") (pin "2") (pinfunction "2_2") (pintype "passive"))
      (node (ref "D10") (pin "1") (pinfunction "A_1") (pintype "passive"))
      (node (ref "D11") (pin "A") (pinfunction "A_A") (pintype "passive"))
      (node (ref "D7") (pin "1") (pinfunction "A_1") (pintype "passive"))
      (node (ref "D8") (pin "1") (pinfunction "A_1") (pintype "passive"))
      (node (ref "D9") (pin "1") (pinfunction "A_1") (pintype "passive"))
      (node (ref "IC1") (pin "11") (pinfunction "V-_11") (pintype "power_in"))
      (node (ref "IC3") (pin "2") (pinfunction "GND_2") (pintype "passive"))
      (node (ref "IC4") (pin "11") (pinfunction "V-_11") (pintype "power_in"))
      (node (ref "IC5") (pin "1") (pinfunction "GND_1") (pintype "input"))
      (node (ref "J1") (pin "1") (pinfunction "1_1") (pintype "passive"))
      (node (ref "J1") (pin "2") (pinfunction "2_2") (pintype "passive"))
      (node (ref "OK1") (pin "3") (pinfunction "E_3") (pintype "passive"))
      (node (ref "OK2") (pin "3") (pinfunction "E_3") (pintype "passive"))
      (node (ref "OK3") (pin "3") (pinfunction "E_3") (pintype "passive"))
      (node (ref "OK4") (pin "3") (pinfunction "E_3") (pintype "passive"))
      (node (ref "OK5") (pin "3") (pinfunction "E_3") (pintype "passive"))
      (node (ref "OK6") (pin "3") (pinfunction "E_3") (pintype "passive"))
      (node (ref "R10") (pin "1") (pinfunction "1_1") (pintype "passive"))
      (node (ref "R12") (pin "1") (pinfunction "1_1") (pintype "passive"))
      (node (ref "R13") (pin "1") (pinfunction "1_1") (pintype "passive"))
      (node (ref "R14") (pin "1") (pinfunction "1_1") (pintype "passive"))
      (node (ref "R17") (pin "1") (pinfunction "1_1") (pintype "passive"))
      (node (ref "R20") (pin "1") (pinfunction "1_1") (pintype "passive"))
      (node (ref "R6") (pin "1") (pinfunction "1_1") (pintype "passive"))
      (node (ref "R8") (pin "1") (pinfunction "1_1") (pintype "passive"))
      (node (ref "T1") (pin "3") (pinfunction "E_3") (pintype "passive"))
      (node (ref "T2") (pin "3") (pinfunction "E_3") (pintype "passive"))
      (node (ref "T3") (pin "3") (pinfunction "E_3") (pintype "passive"))
      (node (ref "T4") (pin "3") (pinfunction "E_3") (pintype "passive"))
      (node (ref "T5") (pin "3") (pinfunction "E_3") (pintype "passive"))
      (node (ref "T6") (pin "3") (pinfunction "E_3") (pintype "passive"))
      (node (ref "X1") (pin "2") (pinfunction "KL_2") (pintype "passive"))
      (node (ref "X2") (pin "2") (pinfunction "KL_2") (pintype "passive"))
      (node (ref "X3") (pin "2") (pinfunction "KL_2") (pintype "passive"))
      (node (ref "X4") (pin "1") (pinfunction "S_1") (pintype "passive"))
      (node (ref "X5") (pin "2") (pinfunction "KL_2") (pintype "passive"))
      (node (ref "X6") (pin "2") (pinfunction "KL_2") (pintype "passive"))
      (node (ref "X7") (pin "2") (pinfunction "KL_2") (pintype "passive"))
      (node (ref "X8") (pin "2") (pinfunction "KL_2") (pintype "passive"))
      (node (ref "X9") (pin "2") (pinfunction "KL_2") (pintype "passive"))
    )
    (net (code "52") (name "Net-(D1-PadA)") (class "Default")
      (node (ref "D1") (pin "A") (pinfunction "A_A") (pintype "passive"))
      (node (ref "K1") (pin "2") (pinfunction "2_2") (pintype "passive"))
      (node (ref "T1") (pin "2") (pinfunction "C_2") (pintype "passive"))
      (node (ref "T1") (pin "4") (pinfunction "C_4") (pintype "passive"))
    )
    (net (code "53") (name "Net-(D2-PadA)") (class "Default")
      (node (ref "D2") (pin "A") (pinfunction "A_A") (pintype "passive"))
      (node (ref "K2") (pin "2") (pinfunction "2_2") (pintype "passive"))
      (node (ref "T2") (pin "2") (pinfunction "C_2") (pintype "passive"))
      (node (ref "T2") (pin "4") (pinfunction "C_4") (pintype "passive"))
    )
    (net (code "54") (name "Net-(D3-PadA)") (class "Default")
      (node (ref "D3") (pin "A") (pinfunction "A_A") (pintype "passive"))
      (node (ref "K3") (pin "2") (pinfunction "2_2") (pintype "passive"))
      (node (ref "T3") (pin "2") (pinfunction "C_2") (pintype "passive"))
      (node (ref "T3") (pin "4") (pinfunction "C_4") (pintype "passive"))
    )
    (net (code "55") (name "Net-(D4-PadA)") (class "Default")
      (node (ref "D4") (pin "A") (pinfunction "A_A") (pintype "passive"))
      (node (ref "K4") (pin "2") (pinfunction "2_2") (pintype "passive"))
      (node (ref "T4") (pin "2") (pinfunction "C_2") (pintype "passive"))
      (node (ref "T4") (pin "4") (pinfunction "C_4") (pintype "passive"))
    )
    (net (code "56") (name "Net-(D5-PadA)") (class "Default")
      (node (ref "D5") (pin "A") (pinfunction "A_A") (pintype "passive"))
      (node (ref "K5") (pin "2") (pinfunction "2_2") (pintype "passive"))
      (node (ref "T5") (pin "2") (pinfunction "C_2") (pintype "passive"))
      (node (ref "T5") (pin "4") (pinfunction "C_4") (pintype "passive"))
    )
    (net (code "57") (name "Net-(D6-PadA)") (class "Default")
      (node (ref "D6") (pin "A") (pinfunction "A_A") (pintype "passive"))
      (node (ref "K6") (pin "2") (pinfunction "2_2") (pintype "passive"))
      (node (ref "T6") (pin "2") (pinfunction "C_2") (pintype "passive"))
      (node (ref "T6") (pin "4") (pinfunction "C_4") (pintype "passive"))
    )
    (net (code "58") (name "Net-(F1-1)") (class "Default")
      (node (ref "F1") (pin "1A") (pinfunction "1_1A") (pintype "passive"))
      (node (ref "J1") (pin "3") (pinfunction "3_3") (pintype "passive"))
    )
    (net (code "59") (name "Net-(IC1A-+IN)") (class "Default")
      (node (ref "C4") (pin "1") (pinfunction "1_1") (pintype "passive"))
      (node (ref "IC1") (pin "3") (pinfunction "+IN_3") (pintype "input"))
      (node (ref "R15") (pin "2") (pinfunction "2_2") (pintype "passive"))
    )
    (net (code "60") (name "Net-(IC1A--IN)") (class "Default")
      (node (ref "IC1") (pin "2") (pinfunction "-IN_2") (pintype "input"))
      (node (ref "R13") (pin "2") (pinfunction "2_2") (pintype "passive"))
      (node (ref "R4") (pin "1") (pinfunction "1_1") (pintype "passive"))
    )
    (net (code "61") (name "Net-(IC1B-+IN)") (class "Default")
      (node (ref "C5") (pin "1") (pinfunction "1_1") (pintype "passive"))
      (node (ref "IC1") (pin "5") (pinfunction "+IN_5") (pintype "input"))
      (node (ref "R23") (pin "2") (pinfunction "2_2") (pintype "passive"))
    )
    (net (code "62") (name "Net-(IC1B--IN)") (class "Default")
      (node (ref "IC1") (pin "6") (pinfunction "-IN_6") (pintype "input"))
      (node (ref "R14") (pin "2") (pinfunction "2_2") (pintype "passive"))
      (node (ref "R22") (pin "1") (pinfunction "1_1") (pintype "passive"))
    )
    (net (code "63") (name "Net-(IC1C-+IN)") (class "Default")
      (node (ref "C6") (pin "1") (pinfunction "1_1") (pintype "passive"))
      (node (ref "IC1") (pin "10") (pinfunction "+IN_10") (pintype "input"))
      (node (ref "R18") (pin "2") (pinfunction "2_2") (pintype "passive"))
    )
    (net (code "64") (name "Net-(IC1C--IN)") (class "Default")
      (node (ref "IC1") (pin "9") (pinfunction "-IN_9") (pintype "input"))
      (node (ref "R16") (pin "1") (pinfunction "1_1") (pintype "passive"))
      (node (ref "R17") (pin "2") (pinfunction "2_2") (pintype "passive"))
    )
    (net (code "65") (name "Net-(IC1D-+IN)") (class "Default")
      (node (ref "C7") (pin "1") (pinfunction "1_1") (pintype "passive"))
      (node (ref "IC1") (pin "12") (pinfunction "+IN_12") (pintype "input"))
      (node (ref "R21") (pin "2") (pinfunction "2_2") (pintype "passive"))
    )
    (net (code "66") (name "Net-(IC1D--IN)") (class "Default")
      (node (ref "IC1") (pin "13") (pinfunction "-IN_13") (pintype "input"))
      (node (ref "R19") (pin "1") (pinfunction "1_1") (pintype "passive"))
      (node (ref "R20") (pin "2") (pinfunction "2_2") (pintype "passive"))
    )
    (net (code "67") (name "Net-(IC4A--IN)") (class "Default")
      (node (ref "IC4") (pin "1") (pinfunction "OUT_1") (pintype "output"))
      (node (ref "IC4") (pin "2") (pinfunction "-IN_2") (pintype "input"))
      (node (ref "R5") (pin "2") (pinfunction "2_2") (pintype "passive"))
    )
    (net (code "68") (name "Net-(IC4B--IN)") (class "Default")
      (node (ref "IC4") (pin "6") (pinfunction "-IN_6") (pintype "input"))
      (node (ref "IC4") (pin "7") (pinfunction "OUT_7") (pintype "output"))
      (node (ref "R7") (pin "2") (pinfunction "2_2") (pintype "passive"))
    )
    (net (code "69") (name "Net-(IC4C--IN)") (class "Default")
      (node (ref "IC4") (pin "8") (pinfunction "OUT_8") (pintype "output"))
      (node (ref "IC4") (pin "9") (pinfunction "-IN_9") (pintype "input"))
      (node (ref "R9") (pin "2") (pinfunction "2_2") (pintype "passive"))
    )
    (net (code "70") (name "Net-(IC4D--IN)") (class "Default")
      (node (ref "IC4") (pin "13") (pinfunction "-IN_13") (pintype "input"))
      (node (ref "IC4") (pin "14") (pinfunction "OUT_14") (pintype "output"))
      (node (ref "R11") (pin "2") (pinfunction "2_2") (pintype "passive"))
    )
    (net (code "71") (name "Net-(OK1-AC2)") (class "Default")
      (node (ref "OK1") (pin "2") (pinfunction "AC2_2") (pintype "passive"))
      (node (ref "R3") (pin "2") (pinfunction "2_2") (pintype "passive"))
    )
    (net (code "72") (name "Net-(OK2-AC2)") (class "Default")
      (node (ref "OK2") (pin "2") (pinfunction "AC2_2") (pintype "passive"))
      (node (ref "R1") (pin "2") (pinfunction "2_2") (pintype "passive"))
    )
    (net (code "73") (name "Net-(OK3-AC2)") (class "Default")
      (node (ref "OK3") (pin "2") (pinfunction "AC2_2") (pintype "passive"))
      (node (ref "R24") (pin "2") (pinfunction "2_2") (pintype "passive"))
    )
    (net (code "74") (name "Net-(OK4-AC2)") (class "Default")
      (node (ref "OK4") (pin "2") (pinfunction "AC2_2") (pintype "passive"))
      (node (ref "R2") (pin "2") (pinfunction "2_2") (pintype "passive"))
    )
    (net (code "75") (name "Net-(OK5-AC2)") (class "Default")
      (node (ref "OK5") (pin "2") (pinfunction "AC2_2") (pintype "passive"))
      (node (ref "R30") (pin "2") (pinfunction "2_2") (pintype "passive"))
    )
    (net (code "76") (name "Net-(OK6-AC2)") (class "Default")
      (node (ref "OK6") (pin "2") (pinfunction "AC2_2") (pintype "passive"))
      (node (ref "R29") (pin "2") (pinfunction "2_2") (pintype "passive"))
    )
    (net (code "77") (name "Net-(T1-B)") (class "Default")
      (node (ref "R40") (pin "2") (pinfunction "2_2") (pintype "passive"))
      (node (ref "T1") (pin "1") (pinfunction "B_1") (pintype "passive"))
    )
    (net (code "78") (name "Net-(T2-B)") (class "Default")
      (node (ref "R41") (pin "2") (pinfunction "2_2") (pintype "passive"))
      (node (ref "T2") (pin "1") (pinfunction "B_1") (pintype "passive"))
    )
    (net (code "79") (name "Net-(T3-B)") (class "Default")
      (node (ref "R42") (pin "2") (pinfunction "2_2") (pintype "passive"))
      (node (ref "T3") (pin "1") (pinfunction "B_1") (pintype "passive"))
    )
    (net (code "80") (name "Net-(T4-B)") (class "Default")
      (node (ref "R43") (pin "2") (pinfunction "2_2") (pintype "passive"))
      (node (ref "T4") (pin "1") (pinfunction "B_1") (pintype "passive"))
    )
    (net (code "81") (name "Net-(T5-B)") (class "Default")
      (node (ref "R44") (pin "2") (pinfunction "2_2") (pintype "passive"))
      (node (ref "T5") (pin "1") (pinfunction "B_1") (pintype "passive"))
    )
    (net (code "82") (name "Net-(T6-B)") (class "Default")
      (node (ref "R45") (pin "2") (pinfunction "2_2") (pintype "passive"))
      (node (ref "T6") (pin "1") (pinfunction "B_1") (pintype "passive"))
    )
    (net (code "83") (name "PWM0") (class "Default")
      (node (ref "R15") (pin "1") (pinfunction "1_1") (pintype "passive"))
      (node (ref "X11") (pin "1") (pinfunction "S_1") (pintype "passive"))
    )
    (net (code "84") (name "PWM1") (class "Default")
      (node (ref "R23") (pin "1") (pinfunction "1_1") (pintype "passive"))
      (node (ref "X11") (pin "2") (pinfunction "S_2") (pintype "passive"))
    )
    (net (code "85") (name "PWM2") (class "Default")
      (node (ref "R18") (pin "1") (pinfunction "1_1") (pintype "passive"))
      (node (ref "X11") (pin "3") (pinfunction "S_3") (pintype "passive"))
    )
    (net (code "86") (name "PWM3") (class "Default")
      (node (ref "R21") (pin "1") (pinfunction "1_1") (pintype "passive"))
      (node (ref "X11") (pin "4") (pinfunction "S_4") (pintype "passive"))
    )
    (net (code "87") (name "VDD") (class "Default")
      (node (ref "C1") (pin "1") (pinfunction "1_1") (pintype "passive"))
      (node (ref "D1") (pin "C") (pinfunction "C_C") (pintype "passive"))
      (node (ref "D11") (pin "C") (pinfunction "C_C") (pintype "passive"))
      (node (ref "D2") (pin "C") (pinfunction "C_C") (pintype "passive"))
      (node (ref "D3") (pin "C") (pinfunction "C_C") (pintype "passive"))
      (node (ref "D4") (pin "C") (pinfunction "C_C") (pintype "passive"))
      (node (ref "D5") (pin "C") (pinfunction "C_C") (pintype "passive"))
      (node (ref "D6") (pin "C") (pinfunction "C_C") (pintype "passive"))
      (node (ref "F1") (pin "2A") (pinfunction "2_2A") (pintype "passive"))
      (node (ref "IC1") (pin "4") (pinfunction "V+_4") (pintype "power_in"))
      (node (ref "IC3") (pin "1") (pinfunction "VI_1") (pintype "input"))
      (node (ref "IC4") (pin "4") (pinfunction "V+_4") (pintype "power_in"))
      (node (ref "K1") (pin "1") (pinfunction "1_1") (pintype "passive"))
      (node (ref "K2") (pin "1") (pinfunction "1_1") (pintype "passive"))
      (node (ref "K3") (pin "1") (pinfunction "1_1") (pintype "passive"))
      (node (ref "K4") (pin "1") (pinfunction "1_1") (pintype "passive"))
      (node (ref "K5") (pin "1") (pinfunction "1_1") (pintype "passive"))
      (node (ref "K6") (pin "1") (pinfunction "1_1") (pintype "passive"))
    )
    (net (code "88") (name "unconnected-(K1-PadO)") (class "Default")
      (node (ref "K1") (pin "O") (pinfunction "O_O") (pintype "passive"))
    )
    (net (code "89") (name "unconnected-(K2-PadO)") (class "Default")
      (node (ref "K2") (pin "O") (pinfunction "O_O") (pintype "passive"))
    )
    (net (code "90") (name "unconnected-(K3-PadO)") (class "Default")
      (node (ref "K3") (pin "O") (pinfunction "O_O") (pintype "passive"))
    )
    (net (code "91") (name "unconnected-(K4-PadO)") (class "Default")
      (node (ref "K4") (pin "O") (pinfunction "O_O") (pintype "passive"))
    )
    (net (code "92") (name "unconnected-(K5-PadO)") (class "Default")
      (node (ref "K5") (pin "O") (pinfunction "O_O") (pintype "passive"))
    )
    (net (code "93") (name "unconnected-(K6-PadO)") (class "Default")
      (node (ref "K6") (pin "O") (pinfunction "O_O") (pintype "passive"))
    )
  )
)
